# PowerBoard.net
KiCad netlist of a schematic drawn in Altium Designer
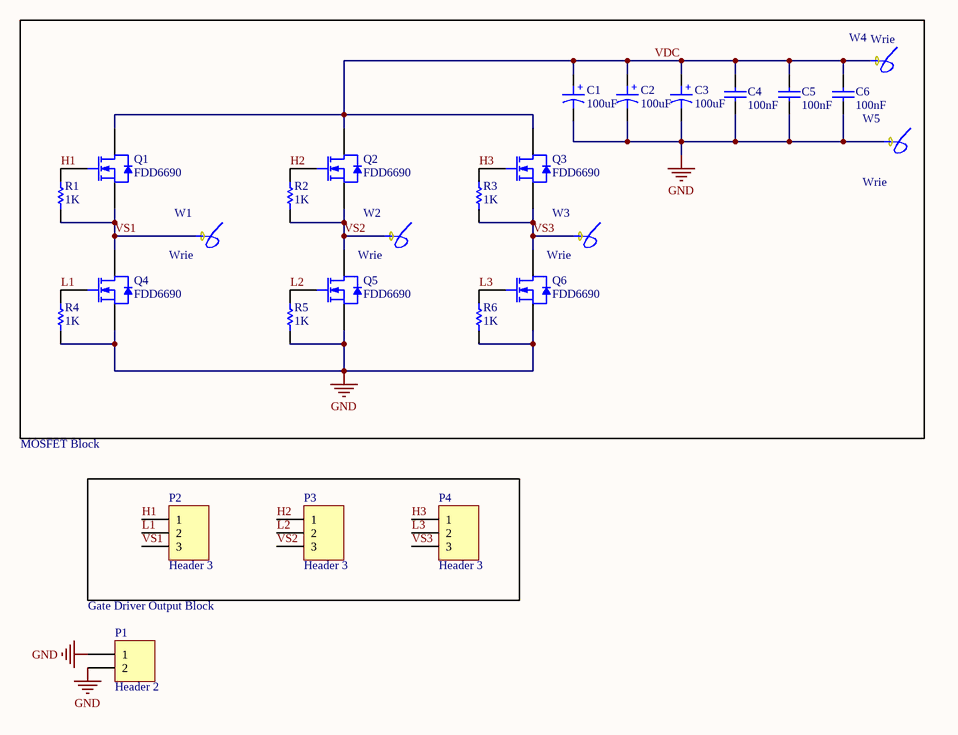
[diagram p0: PowerBoard.SchDoc]

(export (version "E")
  (design (tool "Eeschema 10.0.6"))
  (components
    (comp (ref "C1")
      (value "100uF")
      (footprint "Cap electrolitic radial 6.3x12-2.5")
      (description "Cap electrolitic radial")
      (fields (field (name "DESIGNER") "Abbas Basereh"))
      (libsource (lib "Altium") (part "Cap ELECTROLITIC TOTAL SIZE"))
    )
    (comp (ref "C2")
      (value "100uF")
      (footprint "Cap electrolitic radial 6.3x12-2.5")
      (description "Cap electrolitic radial")
      (fields (field (name "DESIGNER") "Abbas Basereh"))
      (libsource (lib "Altium") (part "Cap ELECTROLITIC TOTAL SIZE"))
    )
    (comp (ref "C3")
      (value "100uF")
      (footprint "Cap electrolitic radial 6.3x12-2.5")
      (description "Cap electrolitic radial")
      (fields (field (name "DESIGNER") "Abbas Basereh"))
      (libsource (lib "Altium") (part "Cap ELECTROLITIC TOTAL SIZE"))
    )
    (comp (ref "C4")
      (value "100nF")
      (footprint "Cap-100nF")
      (description "CAP Ceramic Total")
      (fields (field (name "DESIGNER") "Ali Hafizi"))
      (libsource (lib "Altium") (part "CAP CERAMIC TOTAL SIZE"))
    )
    (comp (ref "C5")
      (value "100nF")
      (footprint "Cap-100nF")
      (description "CAP Ceramic Total")
      (fields (field (name "DESIGNER") "Ali Hafizi"))
      (libsource (lib "Altium") (part "CAP CERAMIC TOTAL SIZE"))
    )
    (comp (ref "C6")
      (value "100nF")
      (footprint "Cap-100nF")
      (description "CAP Ceramic Total")
      (fields (field (name "DESIGNER") "Ali Hafizi"))
      (libsource (lib "Altium") (part "CAP CERAMIC TOTAL SIZE"))
    )
    (comp (ref "P1")
      (value "Header 2")
      (footprint "HDR1X2")
      (description "Header, 2-Pin")
      (fields (field (name "PUBLISHER") "Altium Limited"))
      (libsource (lib "Miscellaneous Connectors") (part "Header 2"))
    )
    (comp (ref "P2")
      (value "Header 3")
      (footprint "HDR1X3")
      (description "Header, 3-Pin")
      (fields (field (name "PUBLISHER") "Altium Limited"))
      (libsource (lib "Altium") (part "Header 3"))
    )
    (comp (ref "P3")
      (value "Header 3")
      (footprint "HDR1X3")
      (description "Header, 3-Pin")
      (fields (field (name "PUBLISHER") "Altium Limited"))
      (libsource (lib "Altium") (part "Header 3"))
    )
    (comp (ref "P4")
      (value "Header 3")
      (footprint "HDR1X3")
      (description "Header, 3-Pin")
      (fields (field (name "PUBLISHER") "Altium Limited"))
      (libsource (lib "Altium") (part "Header 3"))
    )
    (comp (ref "Q1")
      (value "FDD6690")
      (footprint "TO252-3L")
      (description "N-channel MOSFET")
      (fields (field (name "PUBLISHER") "Abbas Basereh"))
      (libsource (lib "Altium") (part "P0903BDG"))
    )
    (comp (ref "Q2")
      (value "FDD6690")
      (footprint "TO252-3L")
      (description "N-channel MOSFET")
      (fields (field (name "PUBLISHER") "Abbas Basereh"))
      (libsource (lib "Altium") (part "P0903BDG"))
    )
    (comp (ref "Q3")
      (value "FDD6690")
      (footprint "TO252-3L")
      (description "N-channel MOSFET")
      (fields (field (name "PUBLISHER") "Abbas Basereh"))
      (libsource (lib "Altium") (part "P0903BDG"))
    )
    (comp (ref "Q4")
      (value "FDD6690")
      (footprint "TO252-3L")
      (description "N-channel MOSFET")
      (fields (field (name "PUBLISHER") "Abbas Basereh"))
      (libsource (lib "Altium") (part "P0903BDG"))
    )
    (comp (ref "Q5")
      (value "FDD6690")
      (footprint "TO252-3L")
      (description "N-channel MOSFET")
      (fields (field (name "PUBLISHER") "Abbas Basereh"))
      (libsource (lib "Altium") (part "P0903BDG"))
    )
    (comp (ref "Q6")
      (value "FDD6690")
      (footprint "TO252-3L")
      (description "N-channel MOSFET")
      (fields (field (name "PUBLISHER") "Abbas Basereh"))
      (libsource (lib "Altium") (part "P0903BDG"))
    )
    (comp (ref "R1")
      (value "1K")
      (footprint "RES-(1/4)")
      (description "TOTAL DIP RESISTOR PACK")
      (fields (field (name "DESIGNER") "Ali Hafizi"))
      (libsource (lib "Altium") (part "RES DIP PACKAGE"))
    )
    (comp (ref "R2")
      (value "1K")
      (footprint "RES-(1/4)")
      (description "TOTAL DIP RESISTOR PACK")
      (fields (field (name "DESIGNER") "Ali Hafizi"))
      (libsource (lib "Altium") (part "RES DIP PACKAGE"))
    )
    (comp (ref "R3")
      (value "1K")
      (footprint "RES-(1/4)")
      (description "TOTAL DIP RESISTOR PACK")
      (fields (field (name "DESIGNER") "Ali Hafizi"))
      (libsource (lib "Altium") (part "RES DIP PACKAGE"))
    )
    (comp (ref "R4")
      (value "1K")
      (footprint "RES-(1/4)")
      (description "TOTAL DIP RESISTOR PACK")
      (fields (field (name "DESIGNER") "Ali Hafizi"))
      (libsource (lib "Altium") (part "RES DIP PACKAGE"))
    )
    (comp (ref "R5")
      (value "1K")
      (footprint "RES-(1/4)")
      (description "TOTAL DIP RESISTOR PACK")
      (fields (field (name "DESIGNER") "Ali Hafizi"))
      (libsource (lib "Altium") (part "RES DIP PACKAGE"))
    )
    (comp (ref "R6")
      (value "1K")
      (footprint "RES-(1/4)")
      (description "TOTAL DIP RESISTOR PACK")
      (fields (field (name "DESIGNER") "Ali Hafizi"))
      (libsource (lib "Altium") (part "RES DIP PACKAGE"))
    )
    (comp (ref "W1")
      (value "*")
      (footprint "wire 1.5 mm")
      (description "A Customize Component For Single Wire Connection")
      (fields (field (name "DIAMETER") "Wrie") (field (name "DESIGNER") "Saeid Jorablo"))
      (libsource (lib "Altium") (part "Single Wire"))
    )
    (comp (ref "W2")
      (value "*")
      (footprint "wire 1.5 mm")
      (description "A Customize Component For Single Wire Connection")
      (fields (field (name "DIAMETER") "Wrie") (field (name "DESIGNER") "Saeid Jorablo"))
      (libsource (lib "Altium") (part "Single Wire"))
    )
    (comp (ref "W3")
      (value "*")
      (footprint "wire 1.5 mm")
      (description "A Customize Component For Single Wire Connection")
      (fields (field (name "DIAMETER") "Wrie") (field (name "DESIGNER") "Saeid Jorablo"))
      (libsource (lib "Altium") (part "Single Wire"))
    )
    (comp (ref "W4")
      (value "*")
      (footprint "wire 1.5 mm")
      (description "A Customize Component For Single Wire Connection")
      (fields (field (name "DIAMETER") "Wrie") (field (name "DESIGNER") "Saeid Jorablo"))
      (libsource (lib "Altium") (part "Single Wire"))
    )
    (comp (ref "W5")
      (value "*")
      (footprint "wire 1.5 mm")
      (description "A Customize Component For Single Wire Connection")
      (fields (field (name "DIAMETER") "Wrie") (field (name "DESIGNER") "Saeid Jorablo"))
      (libsource (lib "Altium") (part "Single Wire"))
    )
  )
  (nets
    (net (code "1") (name "/H1") (class "Default")
      (node (ref "P2") (pin "1") (pinfunction "1_1") (pintype "passive"))
      (node (ref "Q1") (pin "1") (pinfunction "G_1") (pintype "passive"))
      (node (ref "R1") (pin "1") (pinfunction "1_1") (pintype "passive"))
    )
    (net (code "2") (name "/H2") (class "Default")
      (node (ref "P3") (pin "1") (pinfunction "1_1") (pintype "passive"))
      (node (ref "Q2") (pin "1") (pinfunction "G_1") (pintype "passive"))
      (node (ref "R2") (pin "1") (pinfunction "1_1") (pintype "passive"))
    )
    (net (code "3") (name "/H3") (class "Default")
      (node (ref "P4") (pin "1") (pinfunction "1_1") (pintype "passive"))
      (node (ref "Q3") (pin "1") (pinfunction "G_1") (pintype "passive"))
      (node (ref "R3") (pin "1") (pinfunction "1_1") (pintype "passive"))
    )
    (net (code "4") (name "/L1") (class "Default")
      (node (ref "P2") (pin "2") (pinfunction "2_2") (pintype "passive"))
      (node (ref "Q4") (pin "1") (pinfunction "G_1") (pintype "passive"))
      (node (ref "R4") (pin "1") (pinfunction "1_1") (pintype "passive"))
    )
    (net (code "5") (name "/L2") (class "Default")
      (node (ref "P3") (pin "2") (pinfunction "2_2") (pintype "passive"))
      (node (ref "Q5") (pin "1") (pinfunction "G_1") (pintype "passive"))
      (node (ref "R5") (pin "1") (pinfunction "1_1") (pintype "passive"))
    )
    (net (code "6") (name "/L3") (class "Default")
      (node (ref "P4") (pin "2") (pinfunction "2_2") (pintype "passive"))
      (node (ref "Q6") (pin "1") (pinfunction "G_1") (pintype "passive"))
      (node (ref "R6") (pin "1") (pinfunction "1_1") (pintype "passive"))
    )
    (net (code "7") (name "/VDC") (class "Default")
      (node (ref "C1") (pin "1") (pinfunction "1_1") (pintype "passive"))
      (node (ref "C2") (pin "1") (pinfunction "1_1") (pintype "passive"))
      (node (ref "C3") (pin "1") (pinfunction "1_1") (pintype "passive"))
      (node (ref "C4") (pin "2") (pinfunction "2_2") (pintype "passive"))
      (node (ref "C5") (pin "2") (pinfunction "2_2") (pintype "passive"))
      (node (ref "C6") (pin "2") (pinfunction "2_2") (pintype "passive"))
      (node (ref "Q1") (pin "4") (pinfunction "D_4") (pintype "passive"))
      (node (ref "Q2") (pin "4") (pinfunction "D_4") (pintype "passive"))
      (node (ref "Q3") (pin "4") (pinfunction "D_4") (pintype "passive"))
      (node (ref "W4") (pin "1") (pinfunction "1_1") (pintype "passive"))
    )
    (net (code "8") (name "/VS1") (class "Default")
      (node (ref "P2") (pin "3") (pinfunction "3_3") (pintype "passive"))
      (node (ref "Q1") (pin "3") (pinfunction "S_3") (pintype "passive"))
      (node (ref "Q4") (pin "4") (pinfunction "D_4") (pintype "passive"))
      (node (ref "R1") (pin "2") (pinfunction "2_2") (pintype "passive"))
      (node (ref "W1") (pin "1") (pinfunction "1_1") (pintype "passive"))
    )
    (net (code "9") (name "/VS2") (class "Default")
      (node (ref "P3") (pin "3") (pinfunction "3_3") (pintype "passive"))
      (node (ref "Q2") (pin "3") (pinfunction "S_3") (pintype "passive"))
      (node (ref "Q5") (pin "4") (pinfunction "D_4") (pintype "passive"))
      (node (ref "R2") (pin "2") (pinfunction "2_2") (pintype "passive"))
      (node (ref "W2") (pin "1") (pinfunction "1_1") (pintype "passive"))
    )
    (net (code "10") (name "/VS3") (class "Default")
      (node (ref "P4") (pin "3") (pinfunction "3_3") (pintype "passive"))
      (node (ref "Q3") (pin "3") (pinfunction "S_3") (pintype "passive"))
      (node (ref "Q6") (pin "4") (pinfunction "D_4") (pintype "passive"))
      (node (ref "R3") (pin "2") (pinfunction "2_2") (pintype "passive"))
      (node (ref "W3") (pin "1") (pinfunction "1_1") (pintype "passive"))
    )
    (net (code "11") (name "GND") (class "Default")
      (node (ref "C1") (pin "2") (pinfunction "2_2") (pintype "passive"))
      (node (ref "C2") (pin "2") (pinfunction "2_2") (pintype "passive"))
      (node (ref "C3") (pin "2") (pinfunction "2_2") (pintype "passive"))
      (node (ref "C4") (pin "1") (pinfunction "1_1") (pintype "passive"))
      (node (ref "C5") (pin "1") (pinfunction "1_1") (pintype "passive"))
      (node (ref "C6") (pin "1") (pinfunction "1_1") (pintype "passive"))
      (node (ref "P1") (pin "1") (pinfunction "1_1") (pintype "passive"))
      (node (ref "P1") (pin "2") (pinfunction "2_2") (pintype "passive"))
      (node (ref "Q4") (pin "3") (pinfunction "S_3") (pintype "passive"))
      (node (ref "Q5") (pin "3") (pinfunction "S_3") (pintype "passive"))
      (node (ref "Q6") (pin "3") (pinfunction "S_3") (pintype "passive"))
      (node (ref "R4") (pin "2") (pinfunction "2_2") (pintype "passive"))
      (node (ref "R5") (pin "2") (pinfunction "2_2") (pintype "passive"))
      (node (ref "R6") (pin "2") (pinfunction "2_2") (pintype "passive"))
      (node (ref "W5") (pin "1") (pinfunction "1_1") (pintype "passive"))
    )
  )
)
